# UsbEuroPowerAdaptor.net
KiCad netlist of a schematic drawn in EAGLE
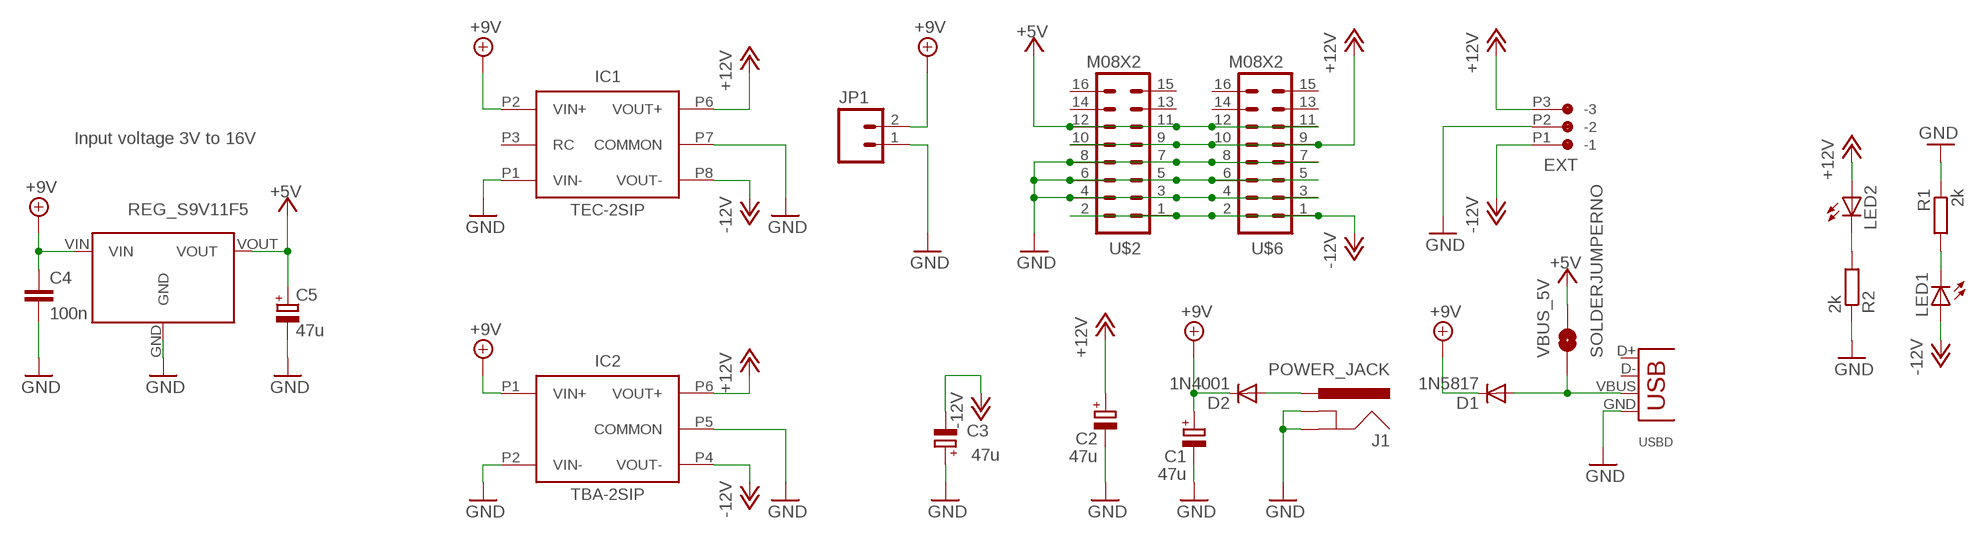
[diagram p0: schematic, sheet 1]

(export (version "E")
  (design (tool "Eeschema 10.0.6"))
  (components
    (comp (ref "C1")
      (value "47u")
      (footprint "eagle-import:E5-6")
      (libsource (lib "eagle-import") (part "CPOL-EUE5-6"))
    )
    (comp (ref "C2")
      (value "47u")
      (footprint "eagle-import:E5-6")
      (libsource (lib "eagle-import") (part "CPOL-EUE5-6"))
    )
    (comp (ref "C3")
      (value "47u")
      (footprint "eagle-import:E5-6")
      (libsource (lib "eagle-import") (part "CPOL-EUE5-6"))
    )
    (comp (ref "C4")
      (value "100n")
      (footprint "eagle-import:C050-024X044")
      (libsource (lib "eagle-import") (part "C-EU050-024X044"))
    )
    (comp (ref "C5")
      (value "47u")
      (footprint "eagle-import:E5-6")
      (libsource (lib "eagle-import") (part "CPOL-EUE5-6"))
    )
    (comp (ref "D1")
      (value "1N5817")
      (footprint "eagle-import:DIODE-1N4001")
      (libsource (lib "eagle-import") (part "DIODEPTH"))
    )
    (comp (ref "D2")
      (value "1N4001")
      (footprint "eagle-import:DIODE-1N4001")
      (libsource (lib "eagle-import") (part "DIODEPTH"))
    )
    (comp (ref "EXT")
      (value "CON-JST_PH_3W")
      (footprint "eagle-import:CON-JST_PH_3W")
      (libsource (lib "eagle-import") (part "CON-JST_PH_3W"))
    )
    (comp (ref "IC1")
      (value "TEC-2SIP")
      (footprint "eagle-import:TEC-2")
      (libsource (lib "eagle-import") (part "TEC-2SIP"))
    )
    (comp (ref "IC2")
      (value "TBA-2SIP")
      (footprint "eagle-import:TBA-2")
      (libsource (lib "eagle-import") (part "TBA-2SIP"))
    )
    (comp (ref "IC3")
      (value "REG_S9V11F5")
      (footprint "eagle-import:REG_S9V11F5")
      (libsource (lib "eagle-import") (part "REG_S9V11F5"))
    )
    (comp (ref "J1")
      (value "POWER_JACK")
      (footprint "eagle-import:DC_JACK_SLOT")
      (libsource (lib "eagle-import") (part "POWER_JACK"))
    )
    (comp (ref "JP1")
      (value "M02PTH")
      (footprint "eagle-import:1X02")
      (libsource (lib "eagle-import") (part "M02PTH"))
    )
    (comp (ref "LED1")
      (value "LED3MM")
      (footprint "eagle-import:LED3MM")
      (libsource (lib "eagle-import") (part "LED3MM"))
    )
    (comp (ref "LED2")
      (value "LED3MM")
      (footprint "eagle-import:LED3MM")
      (libsource (lib "eagle-import") (part "LED3MM"))
    )
    (comp (ref "R1")
      (value "2k")
      (footprint "eagle-import:0204_7")
      (libsource (lib "eagle-import") (part "R-EU_0204/7"))
    )
    (comp (ref "R2")
      (value "2k")
      (footprint "eagle-import:0204_7")
      (libsource (lib "eagle-import") (part "R-EU_0204/7"))
    )
    (comp (ref "U$2")
      (value "M08X2")
      (footprint "eagle-import:2X8")
      (libsource (lib "eagle-import") (part "M08X2"))
    )
    (comp (ref "U$6")
      (value "M08X2")
      (footprint "eagle-import:2X8")
      (libsource (lib "eagle-import") (part "M08X2"))
    )
    (comp (ref "USBD")
      (value "USB-B-H")
      (footprint "eagle-import:USB-B-H")
      (libsource (lib "eagle-import") (part "USB-B-H"))
    )
    (comp (ref "VBUS_5V")
      (value "SOLDERJUMPERNO")
      (footprint "eagle-import:SJ_2S-NO")
      (libsource (lib "eagle-import") (part "SOLDERJUMPERNO"))
    )
  )
  (nets
    (net (code "1") (name "+5V") (class "Default")
      (node (ref "C5") (pin "+") (pinfunction "+_+") (pintype "passive"))
      (node (ref "IC3") (pin "VOUT") (pinfunction "VOUT_VOUT") (pintype "output"))
      (node (ref "U$2") (pin "11") (pinfunction "11_11") (pintype "passive"))
      (node (ref "U$2") (pin "12") (pinfunction "12_12") (pintype "passive"))
      (node (ref "U$6") (pin "11") (pinfunction "11_11") (pintype "passive"))
      (node (ref "U$6") (pin "12") (pinfunction "12_12") (pintype "passive"))
      (node (ref "VBUS_5V") (pin "2") (pinfunction "2_2") (pintype "passive"))
    )
    (net (code "2") (name "+9V") (class "Default")
      (node (ref "C1") (pin "+") (pinfunction "+_+") (pintype "passive"))
      (node (ref "C4") (pin "1") (pinfunction "1_1") (pintype "passive"))
      (node (ref "D1") (pin "C") (pinfunction "C_C") (pintype "passive"))
      (node (ref "D2") (pin "C") (pinfunction "C_C") (pintype "passive"))
      (node (ref "IC1") (pin "P2") (pinfunction "VIN+_P2") (pintype "bidirectional"))
      (node (ref "IC2") (pin "P1") (pinfunction "VIN+_P1") (pintype "bidirectional"))
      (node (ref "IC3") (pin "VIN") (pinfunction "VIN_VIN") (pintype "input"))
      (node (ref "JP1") (pin "2") (pinfunction "2_2") (pintype "passive"))
    )
    (net (code "3") (name "+12V") (class "Default")
      (node (ref "C2") (pin "+") (pinfunction "+_+") (pintype "passive"))
      (node (ref "EXT") (pin "P3") (pinfunction "-3_P3") (pintype "bidirectional"))
      (node (ref "IC1") (pin "P6") (pinfunction "VOUT+_P6") (pintype "bidirectional"))
      (node (ref "IC2") (pin "P6") (pinfunction "VOUT+_P6") (pintype "bidirectional"))
      (node (ref "LED2") (pin "A") (pinfunction "A_A") (pintype "passive"))
      (node (ref "U$2") (pin "10") (pinfunction "10_10") (pintype "passive"))
      (node (ref "U$2") (pin "9") (pinfunction "9_9") (pintype "passive"))
      (node (ref "U$6") (pin "10") (pinfunction "10_10") (pintype "passive"))
      (node (ref "U$6") (pin "9") (pinfunction "9_9") (pintype "passive"))
    )
    (net (code "4") (name "-12V") (class "Default")
      (node (ref "C3") (pin "-") (pinfunction "-_-") (pintype "passive"))
      (node (ref "EXT") (pin "P1") (pinfunction "-1_P1") (pintype "bidirectional"))
      (node (ref "IC1") (pin "P8") (pinfunction "VOUT-_P8") (pintype "bidirectional"))
      (node (ref "IC2") (pin "P4") (pinfunction "VOUT-_P4") (pintype "bidirectional"))
      (node (ref "LED1") (pin "A") (pinfunction "A_A") (pintype "passive"))
      (node (ref "U$2") (pin "1") (pinfunction "1_1") (pintype "passive"))
      (node (ref "U$2") (pin "2") (pinfunction "2_2") (pintype "passive"))
      (node (ref "U$6") (pin "1") (pinfunction "1_1") (pintype "passive"))
      (node (ref "U$6") (pin "2") (pinfunction "2_2") (pintype "passive"))
    )
    (net (code "5") (name "GND") (class "Default")
      (node (ref "C1") (pin "-") (pinfunction "-_-") (pintype "passive"))
      (node (ref "C2") (pin "-") (pinfunction "-_-") (pintype "passive"))
      (node (ref "C3") (pin "+") (pinfunction "+_+") (pintype "passive"))
      (node (ref "C4") (pin "2") (pinfunction "2_2") (pintype "passive"))
      (node (ref "C5") (pin "-") (pinfunction "-_-") (pintype "passive"))
      (node (ref "EXT") (pin "P2") (pinfunction "-2_P2") (pintype "bidirectional"))
      (node (ref "IC1") (pin "P1") (pinfunction "VIN-_P1") (pintype "bidirectional"))
      (node (ref "IC1") (pin "P7") (pinfunction "COMMON_P7") (pintype "bidirectional"))
      (node (ref "IC2") (pin "P2") (pinfunction "VIN-_P2") (pintype "bidirectional"))
      (node (ref "IC2") (pin "P5") (pinfunction "COMMON_P5") (pintype "bidirectional"))
      (node (ref "IC3") (pin "GND") (pinfunction "GND_GND") (pintype "power_in"))
      (node (ref "J1") (pin "GND") (pinfunction "GND_GND") (pintype "bidirectional"))
      (node (ref "J1") (pin "GNDBREAK") (pinfunction "GNDBREAK_GNDBREAK") (pintype "bidirectional"))
      (node (ref "JP1") (pin "1") (pinfunction "1_1") (pintype "passive"))
      (node (ref "R1") (pin "1") (pinfunction "1_1") (pintype "passive"))
      (node (ref "R2") (pin "1") (pinfunction "1_1") (pintype "passive"))
      (node (ref "U$2") (pin "3") (pinfunction "3_3") (pintype "passive"))
      (node (ref "U$2") (pin "4") (pinfunction "4_4") (pintype "passive"))
      (node (ref "U$2") (pin "5") (pinfunction "5_5") (pintype "passive"))
      (node (ref "U$2") (pin "6") (pinfunction "6_6") (pintype "passive"))
      (node (ref "U$2") (pin "7") (pinfunction "7_7") (pintype "passive"))
      (node (ref "U$2") (pin "8") (pinfunction "8_8") (pintype "passive"))
      (node (ref "U$6") (pin "3") (pinfunction "3_3") (pintype "passive"))
      (node (ref "U$6") (pin "4") (pinfunction "4_4") (pintype "passive"))
      (node (ref "U$6") (pin "5") (pinfunction "5_5") (pintype "passive"))
      (node (ref "U$6") (pin "6") (pinfunction "6_6") (pintype "passive"))
      (node (ref "U$6") (pin "7") (pinfunction "7_7") (pintype "passive"))
      (node (ref "U$6") (pin "8") (pinfunction "8_8") (pintype "passive"))
      (node (ref "USBD") (pin "GND") (pinfunction "GND_GND") (pintype "bidirectional"))
    )
    (net (code "6") (name "Net-(D1-PadA)") (class "Default")
      (node (ref "D1") (pin "A") (pinfunction "A_A") (pintype "passive"))
      (node (ref "USBD") (pin "VBUS") (pinfunction "VBUS_VBUS") (pintype "bidirectional"))
      (node (ref "VBUS_5V") (pin "1") (pinfunction "1_1") (pintype "passive"))
    )
    (net (code "7") (name "Net-(D2-PadA)") (class "Default")
      (node (ref "D2") (pin "A") (pinfunction "A_A") (pintype "passive"))
      (node (ref "J1") (pin "PWR") (pinfunction "PWR_PWR") (pintype "bidirectional"))
    )
    (net (code "8") (name "Net-(LED1-C)") (class "Default")
      (node (ref "LED1") (pin "K") (pinfunction "C_K") (pintype "passive"))
      (node (ref "R1") (pin "2") (pinfunction "2_2") (pintype "passive"))
    )
    (net (code "9") (name "Net-(LED2-C)") (class "Default")
      (node (ref "LED2") (pin "K") (pinfunction "C_K") (pintype "passive"))
      (node (ref "R2") (pin "2") (pinfunction "2_2") (pintype "passive"))
    )
    (net (code "10") (name "unconnected-(IC1-RC-PadP3)") (class "Default")
      (node (ref "IC1") (pin "P3") (pinfunction "RC_P3") (pintype "bidirectional"))
    )
    (net (code "11") (name "unconnected-(U$2-Pad13)") (class "Default")
      (node (ref "U$2") (pin "13") (pinfunction "13_13") (pintype "passive"))
    )
    (net (code "12") (name "unconnected-(U$2-Pad14)") (class "Default")
      (node (ref "U$2") (pin "14") (pinfunction "14_14") (pintype "passive"))
    )
    (net (code "13") (name "unconnected-(U$2-Pad15)") (class "Default")
      (node (ref "U$2") (pin "15") (pinfunction "15_15") (pintype "passive"))
    )
    (net (code "14") (name "unconnected-(U$2-Pad16)") (class "Default")
      (node (ref "U$2") (pin "16") (pinfunction "16_16") (pintype "passive"))
    )
    (net (code "15") (name "unconnected-(U$6-Pad13)") (class "Default")
      (node (ref "U$6") (pin "13") (pinfunction "13_13") (pintype "passive"))
    )
    (net (code "16") (name "unconnected-(U$6-Pad14)") (class "Default")
      (node (ref "U$6") (pin "14") (pinfunction "14_14") (pintype "passive"))
    )
    (net (code "17") (name "unconnected-(U$6-Pad15)") (class "Default")
      (node (ref "U$6") (pin "15") (pinfunction "15_15") (pintype "passive"))
    )
    (net (code "18") (name "unconnected-(U$6-Pad16)") (class "Default")
      (node (ref "U$6") (pin "16") (pinfunction "16_16") (pintype "passive"))
    )
    (net (code "19") (name "unconnected-(USBD-PadD+)") (class "Default")
      (node (ref "USBD") (pin "D+") (pinfunction "D+_D+") (pintype "bidirectional"))
    )
    (net (code "20") (name "unconnected-(USBD-PadD-)") (class "Default")
      (node (ref "USBD") (pin "D-") (pinfunction "D-_D-") (pintype "bidirectional"))
    )
  )
)
